# BreadBoard.net
KiCad netlist of a schematic drawn in EAGLE
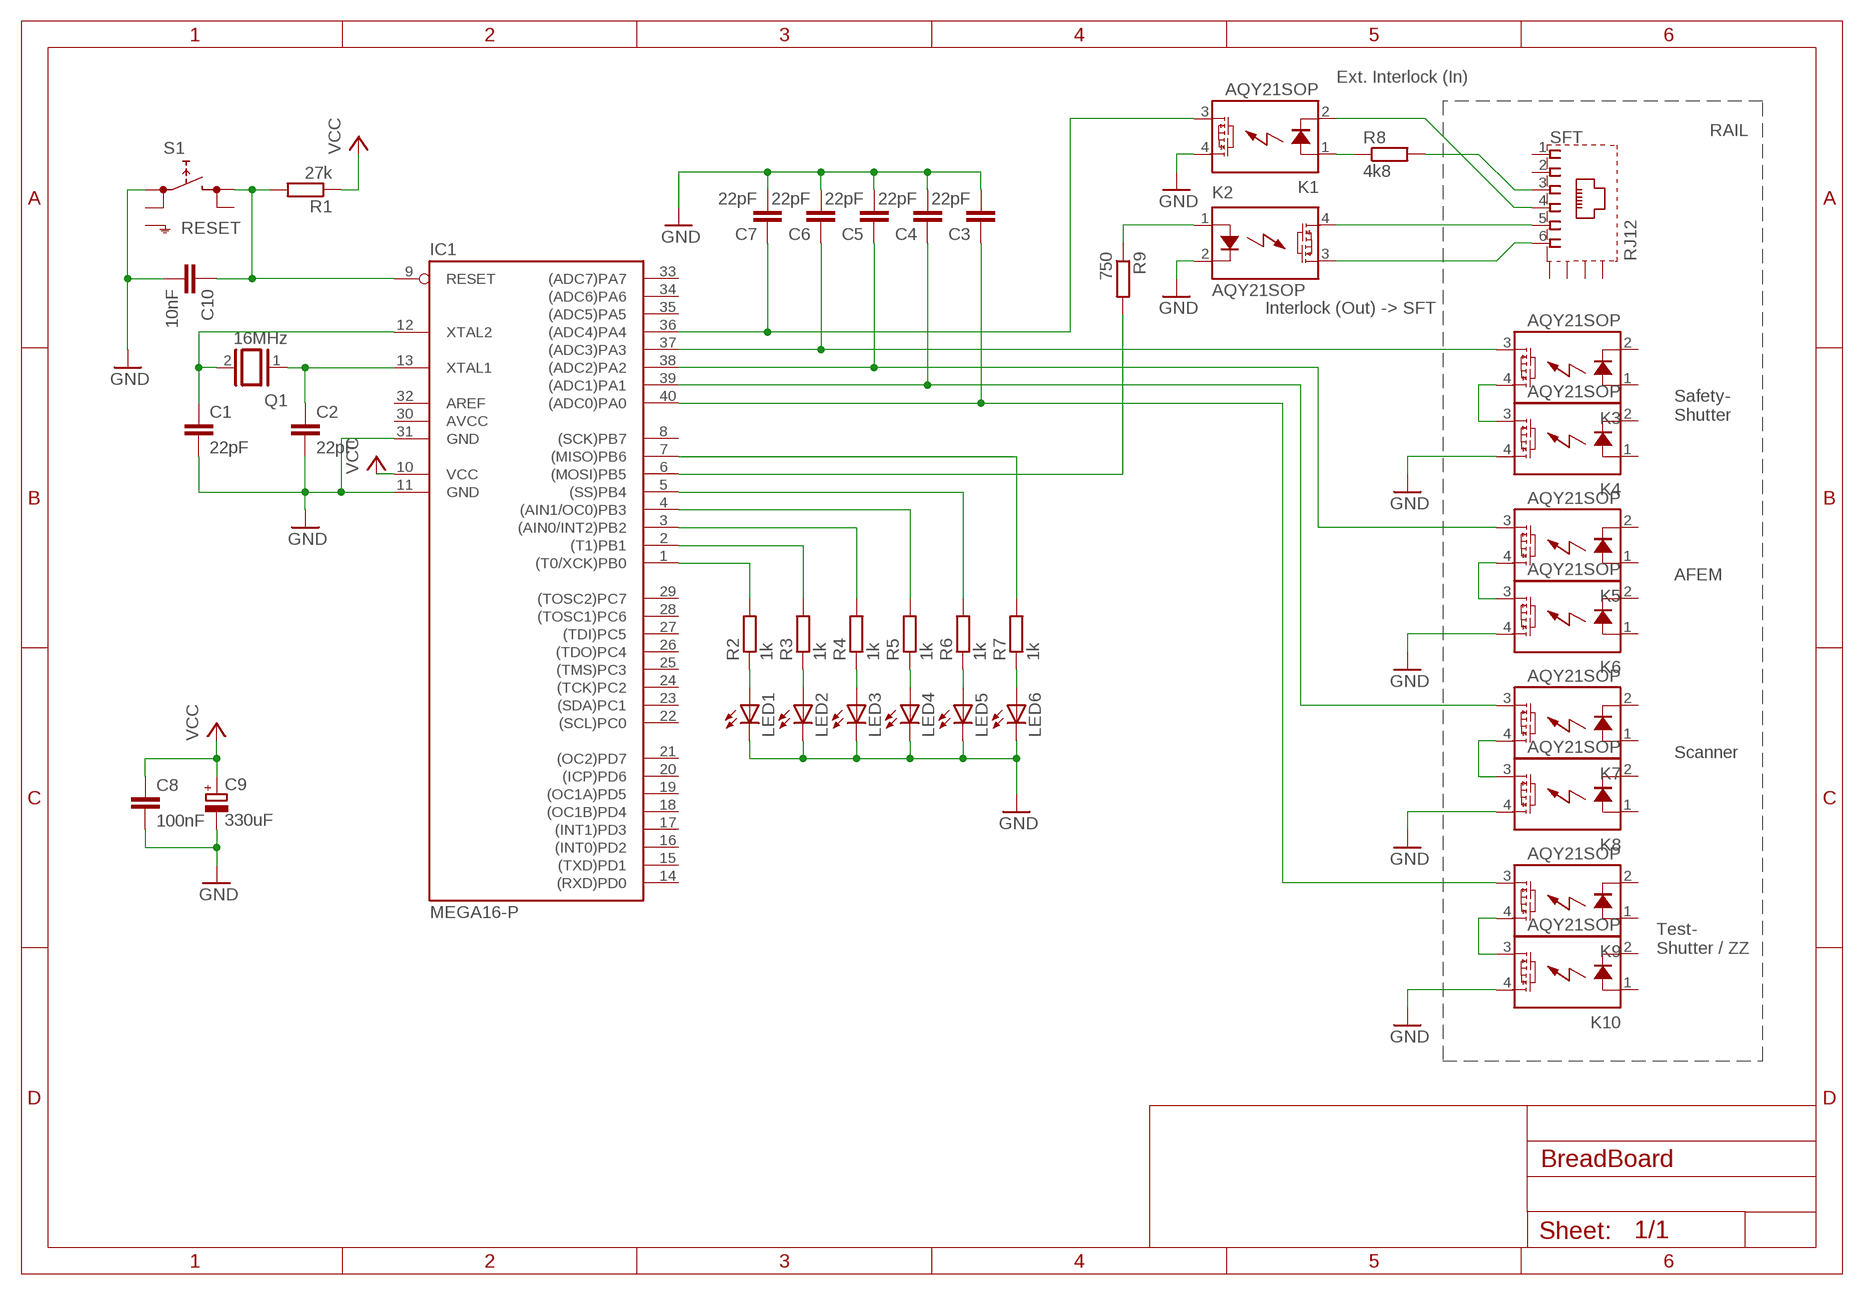
[diagram p0: schematic, sheet 1]

(export (version "E")
  (design (tool "Eeschema 10.0.6"))
  (components
    (comp (ref "C1")
      (value "22pF")
      (footprint "eagle-import:C025-025X050")
      (libsource (lib "eagle-import") (part "C-EU025-025X050"))
    )
    (comp (ref "C2")
      (value "22pF")
      (footprint "eagle-import:C025-025X050")
      (libsource (lib "eagle-import") (part "C-EU025-025X050"))
    )
    (comp (ref "C3")
      (value "22pF")
      (footprint "eagle-import:C025-025X050")
      (libsource (lib "eagle-import") (part "C-EU025-025X050"))
    )
    (comp (ref "C4")
      (value "22pF")
      (footprint "eagle-import:C025-025X050")
      (libsource (lib "eagle-import") (part "C-EU025-025X050"))
    )
    (comp (ref "C5")
      (value "22pF")
      (footprint "eagle-import:C025-025X050")
      (libsource (lib "eagle-import") (part "C-EU025-025X050"))
    )
    (comp (ref "C6")
      (value "22pF")
      (footprint "eagle-import:C025-025X050")
      (libsource (lib "eagle-import") (part "C-EU025-025X050"))
    )
    (comp (ref "C7")
      (value "22pF")
      (footprint "eagle-import:C025-025X050")
      (libsource (lib "eagle-import") (part "C-EU025-025X050"))
    )
    (comp (ref "C8")
      (value "100nF")
      (footprint "eagle-import:C025-025X050")
      (libsource (lib "eagle-import") (part "C-EU025-025X050"))
    )
    (comp (ref "C9")
      (value "330uF")
      (footprint "eagle-import:E2,5-7")
      (libsource (lib "eagle-import") (part "CPOL-EUE2.5-7"))
    )
    (comp (ref "C10")
      (value "10nF")
      (footprint "eagle-import:C025-025X050")
      (libsource (lib "eagle-import") (part "C-EU025-025X050"))
    )
    (comp (ref "IC1")
      (value "MEGA16-P")
      (footprint "eagle-import:DIL40")
      (fields (field (name "MPN") "ATMEGA16-16PU"))
      (libsource (lib "eagle-import") (part "MEGA16-P"))
    )
    (comp (ref "K1")
      (value "AQY21SOP")
      (footprint "eagle-import:SOP04")
      (libsource (lib "eagle-import") (part "AQYSOP21"))
    )
    (comp (ref "K2")
      (value "AQY21SOP")
      (footprint "eagle-import:SOP04")
      (libsource (lib "eagle-import") (part "AQYSOP21"))
    )
    (comp (ref "K3")
      (value "AQY21SOP")
      (footprint "eagle-import:SOP04")
      (libsource (lib "eagle-import") (part "AQYSOP21"))
    )
    (comp (ref "K4")
      (value "AQY21SOP")
      (footprint "eagle-import:SOP04")
      (libsource (lib "eagle-import") (part "AQYSOP21"))
    )
    (comp (ref "K5")
      (value "AQY21SOP")
      (footprint "eagle-import:SOP04")
      (libsource (lib "eagle-import") (part "AQYSOP21"))
    )
    (comp (ref "K6")
      (value "AQY21SOP")
      (footprint "eagle-import:SOP04")
      (libsource (lib "eagle-import") (part "AQYSOP21"))
    )
    (comp (ref "K7")
      (value "AQY21SOP")
      (footprint "eagle-import:SOP04")
      (libsource (lib "eagle-import") (part "AQYSOP21"))
    )
    (comp (ref "K8")
      (value "AQY21SOP")
      (footprint "eagle-import:SOP04")
      (libsource (lib "eagle-import") (part "AQYSOP21"))
    )
    (comp (ref "K9")
      (value "AQY21SOP")
      (footprint "eagle-import:SOP04")
      (libsource (lib "eagle-import") (part "AQYSOP21"))
    )
    (comp (ref "K10")
      (value "AQY21SOP")
      (footprint "eagle-import:SOP04")
      (libsource (lib "eagle-import") (part "AQYSOP21"))
    )
    (comp (ref "LED1")
      (value "LED3MM")
      (footprint "eagle-import:LED3MM")
      (libsource (lib "eagle-import") (part "LED3MM"))
    )
    (comp (ref "LED2")
      (value "LED3MM")
      (footprint "eagle-import:LED3MM")
      (libsource (lib "eagle-import") (part "LED3MM"))
    )
    (comp (ref "LED3")
      (value "LED3MM")
      (footprint "eagle-import:LED3MM")
      (libsource (lib "eagle-import") (part "LED3MM"))
    )
    (comp (ref "LED4")
      (value "LED3MM")
      (footprint "eagle-import:LED3MM")
      (libsource (lib "eagle-import") (part "LED3MM"))
    )
    (comp (ref "LED5")
      (value "LED3MM")
      (footprint "eagle-import:LED3MM")
      (libsource (lib "eagle-import") (part "LED3MM"))
    )
    (comp (ref "LED6")
      (value "LED3MM")
      (footprint "eagle-import:LED3MM")
      (libsource (lib "eagle-import") (part "LED3MM"))
    )
    (comp (ref "Q1")
      (value "16MHz")
      (footprint "eagle-import:Q")
      (libsource (lib "eagle-import") (part "XTAL"))
    )
    (comp (ref "R1")
      (value "27k")
      (footprint "eagle-import:0411_15")
      (libsource (lib "eagle-import") (part "R-EU_0411/15"))
    )
    (comp (ref "R2")
      (value "1k")
      (footprint "eagle-import:0411_15")
      (libsource (lib "eagle-import") (part "R-EU_0411/15"))
    )
    (comp (ref "R3")
      (value "1k")
      (footprint "eagle-import:0411_15")
      (libsource (lib "eagle-import") (part "R-EU_0411/15"))
    )
    (comp (ref "R4")
      (value "1k")
      (footprint "eagle-import:0411_15")
      (libsource (lib "eagle-import") (part "R-EU_0411/15"))
    )
    (comp (ref "R5")
      (value "1k")
      (footprint "eagle-import:0411_15")
      (libsource (lib "eagle-import") (part "R-EU_0411/15"))
    )
    (comp (ref "R6")
      (value "1k")
      (footprint "eagle-import:0411_15")
      (libsource (lib "eagle-import") (part "R-EU_0411/15"))
    )
    (comp (ref "R7")
      (value "1k")
      (footprint "eagle-import:0411_15")
      (libsource (lib "eagle-import") (part "R-EU_0411/15"))
    )
    (comp (ref "R8")
      (value "4k8")
      (footprint "eagle-import:0411_15")
      (libsource (lib "eagle-import") (part "R-EU_0411/15"))
    )
    (comp (ref "R9")
      (value "750")
      (footprint "eagle-import:0411_15")
      (libsource (lib "eagle-import") (part "R-EU_0411/15"))
    )
    (comp (ref "S1")
      (value "RESET")
      (footprint "eagle-import:SKHMPXE010")
      (libsource (lib "eagle-import") (part "SKHMPE010S"))
    )
    (comp (ref "SFT")
      (value "RJ12")
      (footprint "eagle-import:RJ11-SHIELD2")
      (fields (field (name "MF") "TYCO ELECTRONICS") (field (name "MPN") "RJ11-6L2-S=F9181"))
      (libsource (lib "eagle-import") (part "RJ112-S-6L"))
    )
  )
  (nets
    (net (code "1") (name "/AVCC") (class "Default")
      (node (ref "IC1") (pin "30") (pinfunction "AVCC_30") (pintype "power_in"))
    )
    (net (code "2") (name "GND") (class "Default")
      (node (ref "C1") (pin "2") (pinfunction "2_2") (pintype "passive"))
      (node (ref "C10") (pin "2") (pinfunction "2_2") (pintype "passive"))
      (node (ref "C2") (pin "2") (pinfunction "2_2") (pintype "passive"))
      (node (ref "C3") (pin "2") (pinfunction "2_2") (pintype "passive"))
      (node (ref "C4") (pin "2") (pinfunction "2_2") (pintype "passive"))
      (node (ref "C5") (pin "2") (pinfunction "2_2") (pintype "passive"))
      (node (ref "C6") (pin "2") (pinfunction "2_2") (pintype "passive"))
      (node (ref "C7") (pin "2") (pinfunction "2_2") (pintype "passive"))
      (node (ref "C8") (pin "2") (pinfunction "2_2") (pintype "passive"))
      (node (ref "C9") (pin "-") (pinfunction "-_-") (pintype "passive"))
      (node (ref "IC1") (pin "11") (pinfunction "GND_11") (pintype "power_in"))
      (node (ref "IC1") (pin "31") (pinfunction "GND_31") (pintype "power_in"))
      (node (ref "K1") (pin "4") (pinfunction "DS1_4") (pintype "passive"))
      (node (ref "K10") (pin "4") (pinfunction "DS1_4") (pintype "passive"))
      (node (ref "K2") (pin "2") (pinfunction "K_2") (pintype "passive"))
      (node (ref "K4") (pin "4") (pinfunction "DS1_4") (pintype "passive"))
      (node (ref "K6") (pin "4") (pinfunction "DS1_4") (pintype "passive"))
      (node (ref "K8") (pin "4") (pinfunction "DS1_4") (pintype "passive"))
      (node (ref "LED1") (pin "K") (pinfunction "C_K") (pintype "passive"))
      (node (ref "LED2") (pin "K") (pinfunction "C_K") (pintype "passive"))
      (node (ref "LED3") (pin "K") (pinfunction "C_K") (pintype "passive"))
      (node (ref "LED4") (pin "K") (pinfunction "C_K") (pintype "passive"))
      (node (ref "LED5") (pin "K") (pinfunction "C_K") (pintype "passive"))
      (node (ref "LED6") (pin "K") (pinfunction "C_K") (pintype "passive"))
      (node (ref "S1") (pin "1") (pinfunction "1.1_1") (pintype "passive"))
    )
    (net (code "3") (name "Net-(IC1-(ADC0)PA0)") (class "Default")
      (node (ref "C3") (pin "1") (pinfunction "1_1") (pintype "passive"))
      (node (ref "IC1") (pin "40") (pinfunction "(ADC0)PA0_40") (pintype "bidirectional"))
      (node (ref "K9") (pin "3") (pinfunction "DS2_3") (pintype "passive"))
    )
    (net (code "4") (name "Net-(IC1-(ADC1)PA1)") (class "Default")
      (node (ref "C4") (pin "1") (pinfunction "1_1") (pintype "passive"))
      (node (ref "IC1") (pin "39") (pinfunction "(ADC1)PA1_39") (pintype "bidirectional"))
      (node (ref "K7") (pin "3") (pinfunction "DS2_3") (pintype "passive"))
    )
    (net (code "5") (name "Net-(IC1-(ADC2)PA2)") (class "Default")
      (node (ref "C5") (pin "1") (pinfunction "1_1") (pintype "passive"))
      (node (ref "IC1") (pin "38") (pinfunction "(ADC2)PA2_38") (pintype "bidirectional"))
      (node (ref "K5") (pin "3") (pinfunction "DS2_3") (pintype "passive"))
    )
    (net (code "6") (name "Net-(IC1-(ADC3)PA3)") (class "Default")
      (node (ref "C6") (pin "1") (pinfunction "1_1") (pintype "passive"))
      (node (ref "IC1") (pin "37") (pinfunction "(ADC3)PA3_37") (pintype "bidirectional"))
      (node (ref "K3") (pin "3") (pinfunction "DS2_3") (pintype "passive"))
    )
    (net (code "7") (name "Net-(IC1-(ADC4)PA4)") (class "Default")
      (node (ref "C7") (pin "1") (pinfunction "1_1") (pintype "passive"))
      (node (ref "IC1") (pin "36") (pinfunction "(ADC4)PA4_36") (pintype "bidirectional"))
      (node (ref "K1") (pin "3") (pinfunction "DS2_3") (pintype "passive"))
    )
    (net (code "8") (name "Net-(IC1-(AIN0{slash}INT2)PB2)") (class "Default")
      (node (ref "IC1") (pin "3") (pinfunction "(AIN0/INT2)PB2_3") (pintype "bidirectional"))
      (node (ref "R4") (pin "2") (pinfunction "2_2") (pintype "passive"))
    )
    (net (code "9") (name "Net-(IC1-(AIN1{slash}OC0)PB3)") (class "Default")
      (node (ref "IC1") (pin "4") (pinfunction "(AIN1/OC0)PB3_4") (pintype "bidirectional"))
      (node (ref "R5") (pin "2") (pinfunction "2_2") (pintype "passive"))
    )
    (net (code "10") (name "Net-(IC1-(MISO)PB6)") (class "Default")
      (node (ref "IC1") (pin "7") (pinfunction "(MISO)PB6_7") (pintype "bidirectional"))
      (node (ref "R7") (pin "2") (pinfunction "2_2") (pintype "passive"))
    )
    (net (code "11") (name "Net-(IC1-(MOSI)PB5)") (class "Default")
      (node (ref "IC1") (pin "6") (pinfunction "(MOSI)PB5_6") (pintype "bidirectional"))
      (node (ref "R9") (pin "2") (pinfunction "2_2") (pintype "passive"))
    )
    (net (code "12") (name "Net-(IC1-(SS)PB4)") (class "Default")
      (node (ref "IC1") (pin "5") (pinfunction "(SS)PB4_5") (pintype "bidirectional"))
      (node (ref "R6") (pin "2") (pinfunction "2_2") (pintype "passive"))
    )
    (net (code "13") (name "Net-(IC1-(T0{slash}XCK)PB0)") (class "Default")
      (node (ref "IC1") (pin "1") (pinfunction "(T0/XCK)PB0_1") (pintype "bidirectional"))
      (node (ref "R2") (pin "2") (pinfunction "2_2") (pintype "passive"))
    )
    (net (code "14") (name "Net-(IC1-(T1)PB1)") (class "Default")
      (node (ref "IC1") (pin "2") (pinfunction "(T1)PB1_2") (pintype "bidirectional"))
      (node (ref "R3") (pin "2") (pinfunction "2_2") (pintype "passive"))
    )
    (net (code "15") (name "Net-(IC1-RESET)") (class "Default")
      (node (ref "C10") (pin "1") (pinfunction "1_1") (pintype "passive"))
      (node (ref "IC1") (pin "9") (pinfunction "RESET_9") (pintype "input"))
      (node (ref "R1") (pin "2") (pinfunction "2_2") (pintype "passive"))
      (node (ref "S1") (pin "3") (pinfunction "2.1_3") (pintype "passive"))
    )
    (net (code "16") (name "Net-(IC1-XTAL1)") (class "Default")
      (node (ref "C2") (pin "1") (pinfunction "1_1") (pintype "passive"))
      (node (ref "IC1") (pin "13") (pinfunction "XTAL1_13") (pintype "bidirectional"))
      (node (ref "Q1") (pin "1") (pinfunction "1_1") (pintype "passive"))
    )
    (net (code "17") (name "Net-(IC1-XTAL2)") (class "Default")
      (node (ref "C1") (pin "1") (pinfunction "1_1") (pintype "passive"))
      (node (ref "IC1") (pin "12") (pinfunction "XTAL2_12") (pintype "bidirectional"))
      (node (ref "Q1") (pin "2") (pinfunction "2_2") (pintype "passive"))
    )
    (net (code "18") (name "Net-(K1-A)") (class "Default")
      (node (ref "K1") (pin "1") (pinfunction "A_1") (pintype "passive"))
      (node (ref "R8") (pin "1") (pinfunction "1_1") (pintype "passive"))
    )
    (net (code "19") (name "Net-(K1-K)") (class "Default")
      (node (ref "K1") (pin "2") (pinfunction "K_2") (pintype "passive"))
      (node (ref "SFT") (pin "4") (pinfunction "4_4") (pintype "passive"))
    )
    (net (code "20") (name "Net-(K2-A)") (class "Default")
      (node (ref "K2") (pin "1") (pinfunction "A_1") (pintype "passive"))
      (node (ref "R9") (pin "1") (pinfunction "1_1") (pintype "passive"))
    )
    (net (code "21") (name "Net-(K2-DS1)") (class "Default")
      (node (ref "K2") (pin "4") (pinfunction "DS1_4") (pintype "passive"))
      (node (ref "SFT") (pin "5") (pinfunction "5_5") (pintype "passive"))
    )
    (net (code "22") (name "Net-(K2-DS2)") (class "Default")
      (node (ref "K2") (pin "3") (pinfunction "DS2_3") (pintype "passive"))
      (node (ref "SFT") (pin "6") (pinfunction "6_6") (pintype "passive"))
    )
    (net (code "23") (name "Net-(K3-DS1)") (class "Default")
      (node (ref "K3") (pin "4") (pinfunction "DS1_4") (pintype "passive"))
      (node (ref "K4") (pin "3") (pinfunction "DS2_3") (pintype "passive"))
    )
    (net (code "24") (name "Net-(K5-DS1)") (class "Default")
      (node (ref "K5") (pin "4") (pinfunction "DS1_4") (pintype "passive"))
      (node (ref "K6") (pin "3") (pinfunction "DS2_3") (pintype "passive"))
    )
    (net (code "25") (name "Net-(K7-DS1)") (class "Default")
      (node (ref "K7") (pin "4") (pinfunction "DS1_4") (pintype "passive"))
      (node (ref "K8") (pin "3") (pinfunction "DS2_3") (pintype "passive"))
    )
    (net (code "26") (name "Net-(K10-DS2)") (class "Default")
      (node (ref "K10") (pin "3") (pinfunction "DS2_3") (pintype "passive"))
      (node (ref "K9") (pin "4") (pinfunction "DS1_4") (pintype "passive"))
    )
    (net (code "27") (name "Net-(LED1-PadA)") (class "Default")
      (node (ref "LED1") (pin "A") (pinfunction "A_A") (pintype "passive"))
      (node (ref "R2") (pin "1") (pinfunction "1_1") (pintype "passive"))
    )
    (net (code "28") (name "Net-(LED2-PadA)") (class "Default")
      (node (ref "LED2") (pin "A") (pinfunction "A_A") (pintype "passive"))
      (node (ref "R3") (pin "1") (pinfunction "1_1") (pintype "passive"))
    )
    (net (code "29") (name "Net-(LED3-PadA)") (class "Default")
      (node (ref "LED3") (pin "A") (pinfunction "A_A") (pintype "passive"))
      (node (ref "R4") (pin "1") (pinfunction "1_1") (pintype "passive"))
    )
    (net (code "30") (name "Net-(LED4-PadA)") (class "Default")
      (node (ref "LED4") (pin "A") (pinfunction "A_A") (pintype "passive"))
      (node (ref "R5") (pin "1") (pinfunction "1_1") (pintype "passive"))
    )
    (net (code "31") (name "Net-(LED5-PadA)") (class "Default")
      (node (ref "LED5") (pin "A") (pinfunction "A_A") (pintype "passive"))
      (node (ref "R6") (pin "1") (pinfunction "1_1") (pintype "passive"))
    )
    (net (code "32") (name "Net-(LED6-PadA)") (class "Default")
      (node (ref "LED6") (pin "A") (pinfunction "A_A") (pintype "passive"))
      (node (ref "R7") (pin "1") (pinfunction "1_1") (pintype "passive"))
    )
    (net (code "33") (name "Net-(R8-Pad2)") (class "Default")
      (node (ref "R8") (pin "2") (pinfunction "2_2") (pintype "passive"))
      (node (ref "SFT") (pin "3") (pinfunction "3_3") (pintype "passive"))
    )
    (net (code "34") (name "VCC") (class "Default")
      (node (ref "C8") (pin "1") (pinfunction "1_1") (pintype "passive"))
      (node (ref "C9") (pin "+") (pinfunction "+_+") (pintype "passive"))
      (node (ref "IC1") (pin "10") (pinfunction "VCC_10") (pintype "power_in"))
      (node (ref "R1") (pin "1") (pinfunction "1_1") (pintype "passive"))
    )
    (net (code "35") (name "unconnected-(IC1-(ADC5)PA5-Pad35)") (class "Default")
      (node (ref "IC1") (pin "35") (pinfunction "(ADC5)PA5_35") (pintype "bidirectional"))
    )
    (net (code "36") (name "unconnected-(IC1-(ADC6)PA6-Pad34)") (class "Default")
      (node (ref "IC1") (pin "34") (pinfunction "(ADC6)PA6_34") (pintype "bidirectional"))
    )
    (net (code "37") (name "unconnected-(IC1-(ADC7)PA7-Pad33)") (class "Default")
      (node (ref "IC1") (pin "33") (pinfunction "(ADC7)PA7_33") (pintype "bidirectional"))
    )
    (net (code "38") (name "unconnected-(IC1-(ICP)PD6-Pad20)") (class "Default")
      (node (ref "IC1") (pin "20") (pinfunction "(ICP)PD6_20") (pintype "bidirectional"))
    )
    (net (code "39") (name "unconnected-(IC1-(INT0)PD2-Pad16)") (class "Default")
      (node (ref "IC1") (pin "16") (pinfunction "(INT0)PD2_16") (pintype "bidirectional"))
    )
    (net (code "40") (name "unconnected-(IC1-(INT1)PD3-Pad17)") (class "Default")
      (node (ref "IC1") (pin "17") (pinfunction "(INT1)PD3_17") (pintype "bidirectional"))
    )
    (net (code "41") (name "unconnected-(IC1-(OC1A)PD5-Pad19)") (class "Default")
      (node (ref "IC1") (pin "19") (pinfunction "(OC1A)PD5_19") (pintype "bidirectional"))
    )
    (net (code "42") (name "unconnected-(IC1-(OC1B)PD4-Pad18)") (class "Default")
      (node (ref "IC1") (pin "18") (pinfunction "(OC1B)PD4_18") (pintype "bidirectional"))
    )
    (net (code "43") (name "unconnected-(IC1-(OC2)PD7-Pad21)") (class "Default")
      (node (ref "IC1") (pin "21") (pinfunction "(OC2)PD7_21") (pintype "bidirectional"))
    )
    (net (code "44") (name "unconnected-(IC1-(RXD)PD0-Pad14)") (class "Default")
      (node (ref "IC1") (pin "14") (pinfunction "(RXD)PD0_14") (pintype "bidirectional"))
    )
    (net (code "45") (name "unconnected-(IC1-(SCK)PB7-Pad8)") (class "Default")
      (node (ref "IC1") (pin "8") (pinfunction "(SCK)PB7_8") (pintype "bidirectional"))
    )
    (net (code "46") (name "unconnected-(IC1-(SCL)PC0-Pad22)") (class "Default")
      (node (ref "IC1") (pin "22") (pinfunction "(SCL)PC0_22") (pintype "bidirectional"))
    )
    (net (code "47") (name "unconnected-(IC1-(SDA)PC1-Pad23)") (class "Default")
      (node (ref "IC1") (pin "23") (pinfunction "(SDA)PC1_23") (pintype "bidirectional"))
    )
    (net (code "48") (name "unconnected-(IC1-(TCK)PC2-Pad24)") (class "Default")
      (node (ref "IC1") (pin "24") (pinfunction "(TCK)PC2_24") (pintype "bidirectional"))
    )
    (net (code "49") (name "unconnected-(IC1-(TDI)PC5-Pad27)") (class "Default")
      (node (ref "IC1") (pin "27") (pinfunction "(TDI)PC5_27") (pintype "bidirectional"))
    )
    (net (code "50") (name "unconnected-(IC1-(TDO)PC4-Pad26)") (class "Default")
      (node (ref "IC1") (pin "26") (pinfunction "(TDO)PC4_26") (pintype "bidirectional"))
    )
    (net (code "51") (name "unconnected-(IC1-(TMS)PC3-Pad25)") (class "Default")
      (node (ref "IC1") (pin "25") (pinfunction "(TMS)PC3_25") (pintype "bidirectional"))
    )
    (net (code "52") (name "unconnected-(IC1-(TOSC1)PC6-Pad28)") (class "Default")
      (node (ref "IC1") (pin "28") (pinfunction "(TOSC1)PC6_28") (pintype "bidirectional"))
    )
    (net (code "53") (name "unconnected-(IC1-(TOSC2)PC7-Pad29)") (class "Default")
      (node (ref "IC1") (pin "29") (pinfunction "(TOSC2)PC7_29") (pintype "bidirectional"))
    )
    (net (code "54") (name "unconnected-(IC1-(TXD)PD1-Pad15)") (class "Default")
      (node (ref "IC1") (pin "15") (pinfunction "(TXD)PD1_15") (pintype "bidirectional"))
    )
    (net (code "55") (name "unconnected-(IC1-AREF-Pad32)") (class "Default")
      (node (ref "IC1") (pin "32") (pinfunction "AREF_32") (pintype "passive"))
    )
    (net (code "56") (name "unconnected-(K3-A-Pad1)") (class "Default")
      (node (ref "K3") (pin "1") (pinfunction "A_1") (pintype "passive"))
    )
    (net (code "57") (name "unconnected-(K3-K-Pad2)") (class "Default")
      (node (ref "K3") (pin "2") (pinfunction "K_2") (pintype "passive"))
    )
    (net (code "58") (name "unconnected-(K4-A-Pad1)") (class "Default")
      (node (ref "K4") (pin "1") (pinfunction "A_1") (pintype "passive"))
    )
    (net (code "59") (name "unconnected-(K4-K-Pad2)") (class "Default")
      (node (ref "K4") (pin "2") (pinfunction "K_2") (pintype "passive"))
    )
    (net (code "60") (name "unconnected-(K5-A-Pad1)") (class "Default")
      (node (ref "K5") (pin "1") (pinfunction "A_1") (pintype "passive"))
    )
    (net (code "61") (name "unconnected-(K5-K-Pad2)") (class "Default")
      (node (ref "K5") (pin "2") (pinfunction "K_2") (pintype "passive"))
    )
    (net (code "62") (name "unconnected-(K6-A-Pad1)") (class "Default")
      (node (ref "K6") (pin "1") (pinfunction "A_1") (pintype "passive"))
    )
    (net (code "63") (name "unconnected-(K6-K-Pad2)") (class "Default")
      (node (ref "K6") (pin "2") (pinfunction "K_2") (pintype "passive"))
    )
    (net (code "64") (name "unconnected-(K7-A-Pad1)") (class "Default")
      (node (ref "K7") (pin "1") (pinfunction "A_1") (pintype "passive"))
    )
    (net (code "65") (name "unconnected-(K7-K-Pad2)") (class "Default")
      (node (ref "K7") (pin "2") (pinfunction "K_2") (pintype "passive"))
    )
    (net (code "66") (name "unconnected-(K8-A-Pad1)") (class "Default")
      (node (ref "K8") (pin "1") (pinfunction "A_1") (pintype "passive"))
    )
    (net (code "67") (name "unconnected-(K8-K-Pad2)") (class "Default")
      (node (ref "K8") (pin "2") (pinfunction "K_2") (pintype "passive"))
    )
    (net (code "68") (name "unconnected-(K9-A-Pad1)") (class "Default")
      (node (ref "K9") (pin "1") (pinfunction "A_1") (pintype "passive"))
    )
    (net (code "69") (name "unconnected-(K9-K-Pad2)") (class "Default")
      (node (ref "K9") (pin "2") (pinfunction "K_2") (pintype "passive"))
    )
    (net (code "70") (name "unconnected-(K10-A-Pad1)") (class "Default")
      (node (ref "K10") (pin "1") (pinfunction "A_1") (pintype "passive"))
    )
    (net (code "71") (name "unconnected-(K10-K-Pad2)") (class "Default")
      (node (ref "K10") (pin "2") (pinfunction "K_2") (pintype "passive"))
    )
    (net (code "72") (name "unconnected-(S1-1.2-Pad2)") (class "Default")
      (node (ref "S1") (pin "2") (pinfunction "1.2_2") (pintype "passive"))
    )
    (net (code "73") (name "unconnected-(S1-2.2-Pad4)") (class "Default")
      (node (ref "S1") (pin "4") (pinfunction "2.2_4") (pintype "passive"))
    )
    (net (code "74") (name "unconnected-(S1-SH-Pad5)") (class "Default")
      (node (ref "S1") (pin "5") (pinfunction "SH_5") (pintype "passive"))
    )
    (net (code "75") (name "unconnected-(SFT-Pad1)") (class "Default")
      (node (ref "SFT") (pin "1") (pinfunction "1_1") (pintype "passive"))
    )
    (net (code "76") (name "unconnected-(SFT-Pad2)") (class "Default")
      (node (ref "SFT") (pin "2") (pinfunction "2_2") (pintype "passive"))
    )
    (net (code "77") (name "unconnected-(SFT-S-PadS1)") (class "Default")
      (node (ref "SFT") (pin "S1") (pinfunction "S_S1") (pintype "passive"))
    )
    (net (code "78") (name "unconnected-(SFT-S-PadS2)") (class "Default")
      (node (ref "SFT") (pin "S2") (pinfunction "S_S2") (pintype "passive"))
    )
    (net (code "79") (name "unconnected-(SFT-S-PadS3)") (class "Default")
      (node (ref "SFT") (pin "S3") (pinfunction "S_S3") (pintype "passive"))
    )
    (net (code "80") (name "unconnected-(SFT-S-PadS4)") (class "Default")
      (node (ref "SFT") (pin "S4") (pinfunction "S_S4") (pintype "passive"))
    )
  )
)
